# Diode_SMD_Test.net
KiCad netlist of a schematic drawn in EAGLE
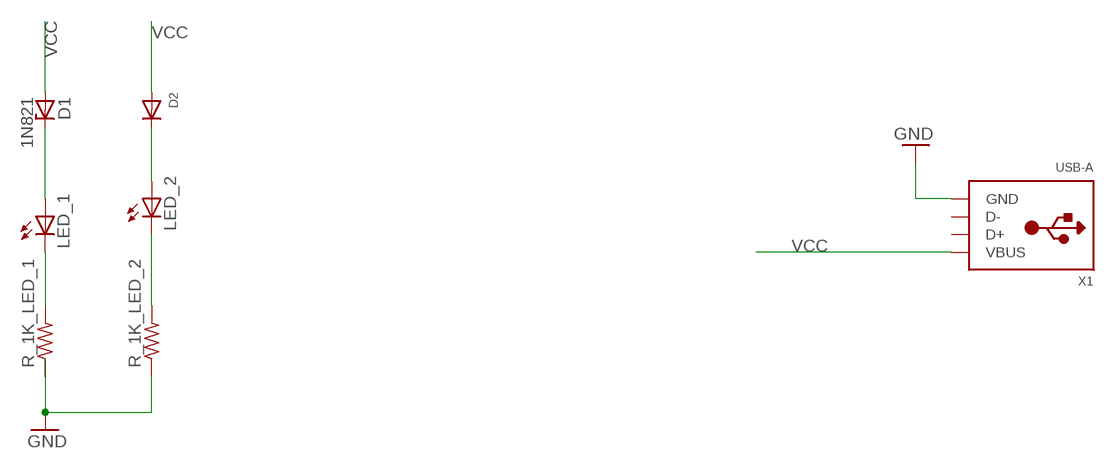
[diagram p0: schematic, sheet 1]

(export (version "E")
  (design (tool "Eeschema 10.0.6"))
  (components
    (comp (ref "D1")
      (value "1N821")
      (footprint "eagle-import:DO35Z10")
      (libsource (lib "eagle-import") (part "1N821"))
    )
    (comp (ref "D2")
      (value "DIODESMA")
      (footprint "eagle-import:SMADIODE")
      (libsource (lib "eagle-import") (part "DIODESMA"))
    )
    (comp (ref "LED_1")
      (value "LEDSMT1206")
      (footprint "eagle-import:1206")
      (libsource (lib "eagle-import") (part "LEDSMT1206"))
    )
    (comp (ref "LED_2")
      (value "LEDSMT1206")
      (footprint "eagle-import:1206")
      (libsource (lib "eagle-import") (part "LEDSMT1206"))
    )
    (comp (ref "R_1K_LED_1")
      (value "R-US_R1206")
      (footprint "eagle-import:R1206")
      (libsource (lib "eagle-import") (part "R-US_R1206"))
    )
    (comp (ref "R_1K_LED_2")
      (value "R-US_R1206")
      (footprint "eagle-import:R1206")
      (libsource (lib "eagle-import") (part "R-US_R1206"))
    )
    (comp (ref "X1")
      (value "USB-A")
      (footprint "eagle-import:MOLEX_480371000")
      (libsource (lib "eagle-import") (part "USB-A"))
    )
  )
  (nets
    (net (code "1") (name "/VCC") (class "Default")
      (node (ref "D1") (pin "A") (pinfunction "A_A") (pintype "passive"))
      (node (ref "D2") (pin "A") (pinfunction "A_A") (pintype "passive"))
      (node (ref "X1") (pin "1") (pinfunction "VBUS_1") (pintype "power_in"))
    )
    (net (code "2") (name "GND") (class "Default")
      (node (ref "R_1K_LED_1") (pin "1") (pinfunction "1_1") (pintype "passive"))
      (node (ref "R_1K_LED_2") (pin "1") (pinfunction "1_1") (pintype "passive"))
      (node (ref "X1") (pin "4") (pinfunction "GND_4") (pintype "power_in"))
    )
    (net (code "3") (name "Net-(D1-PadC)") (class "Default")
      (node (ref "D1") (pin "C") (pinfunction "C_C") (pintype "passive"))
      (node (ref "LED_1") (pin "A") (pinfunction "A_A") (pintype "passive"))
    )
    (net (code "4") (name "Net-(D2-PadC)") (class "Default")
      (node (ref "D2") (pin "C") (pinfunction "C_C") (pintype "passive"))
      (node (ref "LED_2") (pin "A") (pinfunction "A_A") (pintype "passive"))
    )
    (net (code "5") (name "Net-(LED_1-PadC)") (class "Default")
      (node (ref "LED_1") (pin "C") (pinfunction "C_C") (pintype "passive"))
      (node (ref "R_1K_LED_1") (pin "2") (pinfunction "2_2") (pintype "passive"))
    )
    (net (code "6") (name "Net-(LED_2-PadC)") (class "Default")
      (node (ref "LED_2") (pin "C") (pinfunction "C_C") (pintype "passive"))
      (node (ref "R_1K_LED_2") (pin "2") (pinfunction "2_2") (pintype "passive"))
    )
    (net (code "7") (name "unconnected-(X1-D+-Pad3)") (class "Default")
      (node (ref "X1") (pin "3") (pinfunction "D+_3") (pintype "bidirectional"))
    )
    (net (code "8") (name "unconnected-(X1-D--Pad2)") (class "Default")
      (node (ref "X1") (pin "2") (pinfunction "D-_2") (pintype "bidirectional"))
    )
  )
)
